# Load.net
KiCad netlist of a schematic drawn in Altium Designer
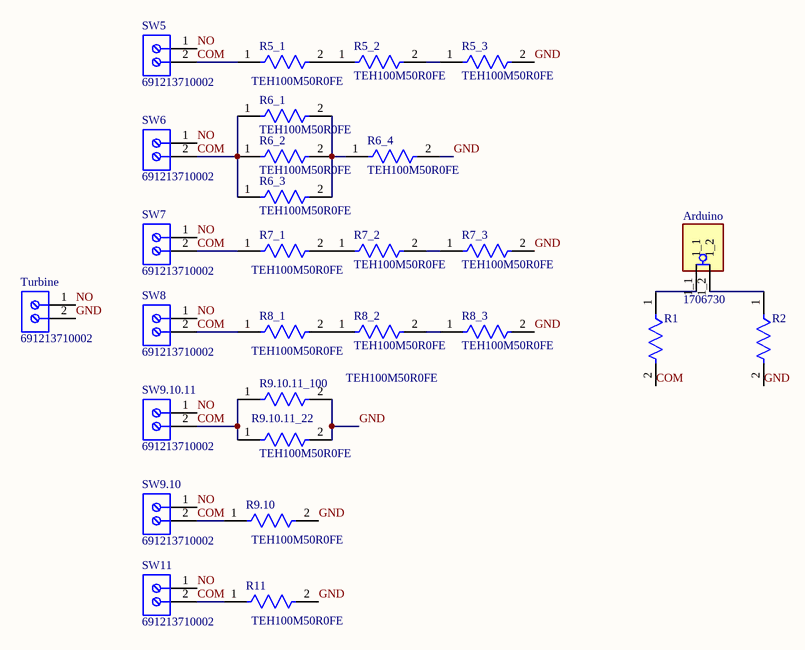
[diagram p0: Load.SchDoc]

(export (version "E")
  (design (tool "Eeschema 10.0.6"))
  (components
    (comp (ref "Arduino")
      (value "1706730")
      (footprint "PHOENIX_1706730")
      (fields (field (name "MF") "{'manufacturer': u'Phoenix Contact'}"))
      (libsource (lib "Capstone") (part "1706730"))
    )
    (comp (ref "R1")
      (value "~")
      (footprint "FP-MRS25-MFG")
      (fields (field (name "TOLERANCE") "1%"))
      (libsource (lib "Altium Content Vault") (part "1029c3af85768c4190bb7ad29bc67b5"))
    )
    (comp (ref "R2")
      (value "~")
      (footprint "FP-MRS25-MFG")
      (fields (field (name "TOLERANCE") "1%"))
      (libsource (lib "Altium Content Vault") (part "1029c3af85768c4190bb7ad29bc67b5"))
    )
    (comp (ref "R5_1")
      (value "TEH100M50R0FE")
      (footprint "FP-TEH100-MFG")
      (description "TEH100M50R0FE Resistor, Thick Film, Res 50 Ohms, Pwr-Rtg100 W, Tol 1%, Radial, TO-247")
      (fields (field (name "TOLERANCE") "1%"))
      (libsource (lib "Altium Content Vault") (part "1029c3af85768c4190bb7ad29bc67b5"))
    )
    (comp (ref "R5_2")
      (value "TEH100M50R0FE")
      (footprint "FP-TEH100-MFG")
      (description "TEH100M50R0FE Resistor, Thick Film, Res 50 Ohms, Pwr-Rtg100 W, Tol 1%, Radial, TO-247")
      (fields (field (name "TOLERANCE") "1%"))
      (libsource (lib "Altium Content Vault") (part "1029c3af85768c4190bb7ad29bc67b5"))
    )
    (comp (ref "R5_3")
      (value "TEH100M50R0FE")
      (footprint "FP-TEH100-MFG")
      (description "TEH100M50R0FE Resistor, Thick Film, Res 50 Ohms, Pwr-Rtg100 W, Tol 1%, Radial, TO-247")
      (fields (field (name "TOLERANCE") "1%"))
      (libsource (lib "Altium Content Vault") (part "1029c3af85768c4190bb7ad29bc67b5"))
    )
    (comp (ref "R6_1")
      (value "TEH100M50R0FE")
      (footprint "FP-TEH100-MFG")
      (description "TEH100M50R0FE Resistor, Thick Film, Res 50 Ohms, Pwr-Rtg100 W, Tol 1%, Radial, TO-247")
      (fields (field (name "TOLERANCE") "1%"))
      (libsource (lib "Altium Content Vault") (part "1029c3af85768c4190bb7ad29bc67b5"))
    )
    (comp (ref "R6_2")
      (value "TEH100M50R0FE")
      (footprint "FP-TEH100-MFG")
      (description "TEH100M50R0FE Resistor, Thick Film, Res 50 Ohms, Pwr-Rtg100 W, Tol 1%, Radial, TO-247")
      (fields (field (name "TOLERANCE") "1%"))
      (libsource (lib "Altium Content Vault") (part "1029c3af85768c4190bb7ad29bc67b5"))
    )
    (comp (ref "R6_3")
      (value "TEH100M50R0FE")
      (footprint "FP-TEH100-MFG")
      (description "TEH100M50R0FE Resistor, Thick Film, Res 50 Ohms, Pwr-Rtg100 W, Tol 1%, Radial, TO-247")
      (fields (field (name "TOLERANCE") "1%"))
      (libsource (lib "Altium Content Vault") (part "1029c3af85768c4190bb7ad29bc67b5"))
    )
    (comp (ref "R6_4")
      (value "TEH100M50R0FE")
      (footprint "FP-TEH100-MFG")
      (description "TEH100M50R0FE Resistor, Thick Film, Res 50 Ohms, Pwr-Rtg100 W, Tol 1%, Radial, TO-247")
      (fields (field (name "TOLERANCE") "1%"))
      (libsource (lib "Altium Content Vault") (part "1029c3af85768c4190bb7ad29bc67b5"))
    )
    (comp (ref "R7_1")
      (value "TEH100M50R0FE")
      (footprint "FP-TEH100-MFG")
      (description "TEH100M50R0FE Resistor, Thick Film, Res 50 Ohms, Pwr-Rtg100 W, Tol 1%, Radial, TO-247")
      (fields (field (name "TOLERANCE") "1%"))
      (libsource (lib "Altium Content Vault") (part "1029c3af85768c4190bb7ad29bc67b5"))
    )
    (comp (ref "R7_2")
      (value "TEH100M50R0FE")
      (footprint "FP-TEH100-MFG")
      (description "TEH100M50R0FE Resistor, Thick Film, Res 50 Ohms, Pwr-Rtg100 W, Tol 1%, Radial, TO-247")
      (fields (field (name "TOLERANCE") "1%"))
      (libsource (lib "Altium Content Vault") (part "1029c3af85768c4190bb7ad29bc67b5"))
    )
    (comp (ref "R7_3")
      (value "TEH100M50R0FE")
      (footprint "FP-TEH100-MFG")
      (description "TEH100M50R0FE Resistor, Thick Film, Res 50 Ohms, Pwr-Rtg100 W, Tol 1%, Radial, TO-247")
      (fields (field (name "TOLERANCE") "1%"))
      (libsource (lib "Altium Content Vault") (part "1029c3af85768c4190bb7ad29bc67b5"))
    )
    (comp (ref "R8_1")
      (value "TEH100M50R0FE")
      (footprint "FP-TEH100-MFG")
      (description "TEH100M50R0FE Resistor, Thick Film, Res 50 Ohms, Pwr-Rtg100 W, Tol 1%, Radial, TO-247")
      (fields (field (name "TOLERANCE") "1%"))
      (libsource (lib "Altium Content Vault") (part "1029c3af85768c4190bb7ad29bc67b5"))
    )
    (comp (ref "R8_2")
      (value "TEH100M50R0FE")
      (footprint "FP-TEH100-MFG")
      (description "TEH100M50R0FE Resistor, Thick Film, Res 50 Ohms, Pwr-Rtg100 W, Tol 1%, Radial, TO-247")
      (fields (field (name "TOLERANCE") "1%"))
      (libsource (lib "Altium Content Vault") (part "1029c3af85768c4190bb7ad29bc67b5"))
    )
    (comp (ref "R8_3")
      (value "TEH100M50R0FE")
      (footprint "FP-TEH100-MFG")
      (description "TEH100M50R0FE Resistor, Thick Film, Res 50 Ohms, Pwr-Rtg100 W, Tol 1%, Radial, TO-247")
      (fields (field (name "TOLERANCE") "1%"))
      (libsource (lib "Altium Content Vault") (part "1029c3af85768c4190bb7ad29bc67b5"))
    )
    (comp (ref "R9.10")
      (value "TEH100M50R0FE")
      (footprint "FP-TEH100-MFG")
      (description "TEH100M50R0FE Resistor, Thick Film, Res 50 Ohms, Pwr-Rtg100 W, Tol 1%, Radial, TO-247")
      (fields (field (name "TOLERANCE") "1%"))
      (libsource (lib "Altium Content Vault") (part "1029c3af85768c4190bb7ad29bc67b5"))
    )
    (comp (ref "R9.10.11_22")
      (value "TEH100M50R0FE")
      (footprint "FP-TEH100-MFG")
      (description "TEH100M50R0FE Resistor, Thick Film, Res 50 Ohms, Pwr-Rtg100 W, Tol 1%, Radial, TO-247")
      (fields (field (name "TOLERANCE") "1%"))
      (libsource (lib "Altium Content Vault") (part "1029c3af85768c4190bb7ad29bc67b5"))
    )
    (comp (ref "R9.10.11_100")
      (value "TEH100M50R0FE")
      (footprint "FP-TEH100-MFG")
      (description "TEH100M50R0FE Resistor, Thick Film, Res 50 Ohms, Pwr-Rtg100 W, Tol 1%, Radial, TO-247")
      (fields (field (name "TOLERANCE") "1%"))
      (libsource (lib "Altium Content Vault") (part "1029c3af85768c4190bb7ad29bc67b5"))
    )
    (comp (ref "R11")
      (value "TEH100M50R0FE")
      (footprint "FP-TEH100-MFG")
      (description "TEH100M50R0FE Resistor, Thick Film, Res 50 Ohms, Pwr-Rtg100 W, Tol 1%, Radial, TO-247")
      (fields (field (name "TOLERANCE") "1%"))
      (libsource (lib "Altium Content Vault") (part "1029c3af85768c4190bb7ad29bc67b5"))
    )
    (comp (ref "SW5")
      (value "691213710002")
      (footprint "691213710002")
      (fields (field (name "VOLTAGE") "300V"))
      (libsource (lib "Altium Content Vault") (part "TBL - 1R - 02P - Screw"))
    )
    (comp (ref "SW6")
      (value "691213710002")
      (footprint "691213710002")
      (fields (field (name "VOLTAGE") "300V"))
      (libsource (lib "Altium Content Vault") (part "TBL - 1R - 02P - Screw"))
    )
    (comp (ref "SW7")
      (value "691213710002")
      (footprint "691213710002")
      (fields (field (name "VOLTAGE") "300V"))
      (libsource (lib "Altium Content Vault") (part "TBL - 1R - 02P - Screw"))
    )
    (comp (ref "SW8")
      (value "691213710002")
      (footprint "691213710002")
      (fields (field (name "VOLTAGE") "300V"))
      (libsource (lib "Altium Content Vault") (part "TBL - 1R - 02P - Screw"))
    )
    (comp (ref "SW9.10")
      (value "691213710002")
      (footprint "691213710002")
      (fields (field (name "VOLTAGE") "300V"))
      (libsource (lib "Altium Content Vault") (part "TBL - 1R - 02P - Screw"))
    )
    (comp (ref "SW9.10.11")
      (value "691213710002")
      (footprint "691213710002")
      (fields (field (name "VOLTAGE") "300V"))
      (libsource (lib "Altium Content Vault") (part "TBL - 1R - 02P - Screw"))
    )
    (comp (ref "SW11")
      (value "691213710002")
      (footprint "691213710002")
      (fields (field (name "VOLTAGE") "300V"))
      (libsource (lib "Altium Content Vault") (part "TBL - 1R - 02P - Screw"))
    )
    (comp (ref "Turbine")
      (value "691213710002")
      (footprint "691213710002")
      (fields (field (name "VOLTAGE") "300V"))
      (libsource (lib "Altium Content Vault") (part "TBL - 1R - 02P - Screw"))
    )
  )
  (nets
    (net (code "1") (name "/COM") (class "Default")
      (node (ref "R1") (pin "2") (pinfunction "2_2") (pintype "passive"))
      (node (ref "R11") (pin "1") (pinfunction "1_1") (pintype "passive"))
      (node (ref "R5_1") (pin "1") (pinfunction "1_1") (pintype "passive"))
      (node (ref "R6_1") (pin "1") (pinfunction "1_1") (pintype "passive"))
      (node (ref "R6_2") (pin "1") (pinfunction "1_1") (pintype "passive"))
      (node (ref "R6_3") (pin "1") (pinfunction "1_1") (pintype "passive"))
      (node (ref "R7_1") (pin "1") (pinfunction "1_1") (pintype "passive"))
      (node (ref "R8_1") (pin "1") (pinfunction "1_1") (pintype "passive"))
      (node (ref "R9.10") (pin "1") (pinfunction "1_1") (pintype "passive"))
      (node (ref "R9.10.11_100") (pin "1") (pinfunction "1_1") (pintype "passive"))
      (node (ref "R9.10.11_22") (pin "1") (pinfunction "1_1") (pintype "passive"))
      (node (ref "SW11") (pin "2") (pinfunction "2_2") (pintype "passive"))
      (node (ref "SW5") (pin "2") (pinfunction "2_2") (pintype "passive"))
      (node (ref "SW6") (pin "2") (pinfunction "2_2") (pintype "passive"))
      (node (ref "SW7") (pin "2") (pinfunction "2_2") (pintype "passive"))
      (node (ref "SW8") (pin "2") (pinfunction "2_2") (pintype "passive"))
      (node (ref "SW9.10") (pin "2") (pinfunction "2_2") (pintype "passive"))
      (node (ref "SW9.10.11") (pin "2") (pinfunction "2_2") (pintype "passive"))
    )
    (net (code "2") (name "/GND") (class "Default")
      (node (ref "R11") (pin "2") (pinfunction "2_2") (pintype "passive"))
      (node (ref "R2") (pin "2") (pinfunction "2_2") (pintype "passive"))
      (node (ref "R5_3") (pin "2") (pinfunction "2_2") (pintype "passive"))
      (node (ref "R6_4") (pin "2") (pinfunction "2_2") (pintype "passive"))
      (node (ref "R7_3") (pin "2") (pinfunction "2_2") (pintype "passive"))
      (node (ref "R8_3") (pin "2") (pinfunction "2_2") (pintype "passive"))
      (node (ref "R9.10") (pin "2") (pinfunction "2_2") (pintype "passive"))
      (node (ref "R9.10.11_100") (pin "2") (pinfunction "2_2") (pintype "passive"))
      (node (ref "R9.10.11_22") (pin "2") (pinfunction "2_2") (pintype "passive"))
      (node (ref "Turbine") (pin "2") (pinfunction "2_2") (pintype "passive"))
    )
    (net (code "3") (name "/NO") (class "Default")
      (node (ref "SW11") (pin "1") (pinfunction "1_1") (pintype "passive"))
      (node (ref "SW5") (pin "1") (pinfunction "1_1") (pintype "passive"))
      (node (ref "SW6") (pin "1") (pinfunction "1_1") (pintype "passive"))
      (node (ref "SW7") (pin "1") (pinfunction "1_1") (pintype "passive"))
      (node (ref "SW8") (pin "1") (pinfunction "1_1") (pintype "passive"))
      (node (ref "SW9.10") (pin "1") (pinfunction "1_1") (pintype "passive"))
      (node (ref "SW9.10.11") (pin "1") (pinfunction "1_1") (pintype "passive"))
      (node (ref "Turbine") (pin "1") (pinfunction "1_1") (pintype "passive"))
    )
    (net (code "4") (name "Net-(Arduino-Pad1_1)") (class "Default")
      (node (ref "Arduino") (pin "1_1") (pinfunction "1_1_1_1") (pintype "passive"))
      (node (ref "R1") (pin "1") (pinfunction "1_1") (pintype "passive"))
    )
    (net (code "5") (name "Net-(Arduino-Pad1_2)") (class "Default")
      (node (ref "Arduino") (pin "1_2") (pinfunction "1_2_1_2") (pintype "passive"))
      (node (ref "R2") (pin "1") (pinfunction "1_1") (pintype "passive"))
    )
    (net (code "6") (name "Net-(R5_1-Pad2)") (class "Default")
      (node (ref "R5_1") (pin "2") (pinfunction "2_2") (pintype "passive"))
      (node (ref "R5_2") (pin "1") (pinfunction "1_1") (pintype "passive"))
    )
    (net (code "7") (name "Net-(R5_2-Pad2)") (class "Default")
      (node (ref "R5_2") (pin "2") (pinfunction "2_2") (pintype "passive"))
      (node (ref "R5_3") (pin "1") (pinfunction "1_1") (pintype "passive"))
    )
    (net (code "8") (name "Net-(R6_1-Pad2)") (class "Default")
      (node (ref "R6_1") (pin "2") (pinfunction "2_2") (pintype "passive"))
      (node (ref "R6_2") (pin "2") (pinfunction "2_2") (pintype "passive"))
      (node (ref "R6_3") (pin "2") (pinfunction "2_2") (pintype "passive"))
      (node (ref "R6_4") (pin "1") (pinfunction "1_1") (pintype "passive"))
    )
    (net (code "9") (name "Net-(R7_1-Pad2)") (class "Default")
      (node (ref "R7_1") (pin "2") (pinfunction "2_2") (pintype "passive"))
      (node (ref "R7_2") (pin "1") (pinfunction "1_1") (pintype "passive"))
    )
    (net (code "10") (name "Net-(R7_2-Pad2)") (class "Default")
      (node (ref "R7_2") (pin "2") (pinfunction "2_2") (pintype "passive"))
      (node (ref "R7_3") (pin "1") (pinfunction "1_1") (pintype "passive"))
    )
    (net (code "11") (name "Net-(R8_1-Pad2)") (class "Default")
      (node (ref "R8_1") (pin "2") (pinfunction "2_2") (pintype "passive"))
      (node (ref "R8_2") (pin "1") (pinfunction "1_1") (pintype "passive"))
    )
    (net (code "12") (name "Net-(R8_2-Pad2)") (class "Default")
      (node (ref "R8_2") (pin "2") (pinfunction "2_2") (pintype "passive"))
      (node (ref "R8_3") (pin "1") (pinfunction "1_1") (pintype "passive"))
    )
  )
)
